# RcMPPT-Power_Module.net
KiCad netlist of a schematic drawn in Altium Designer
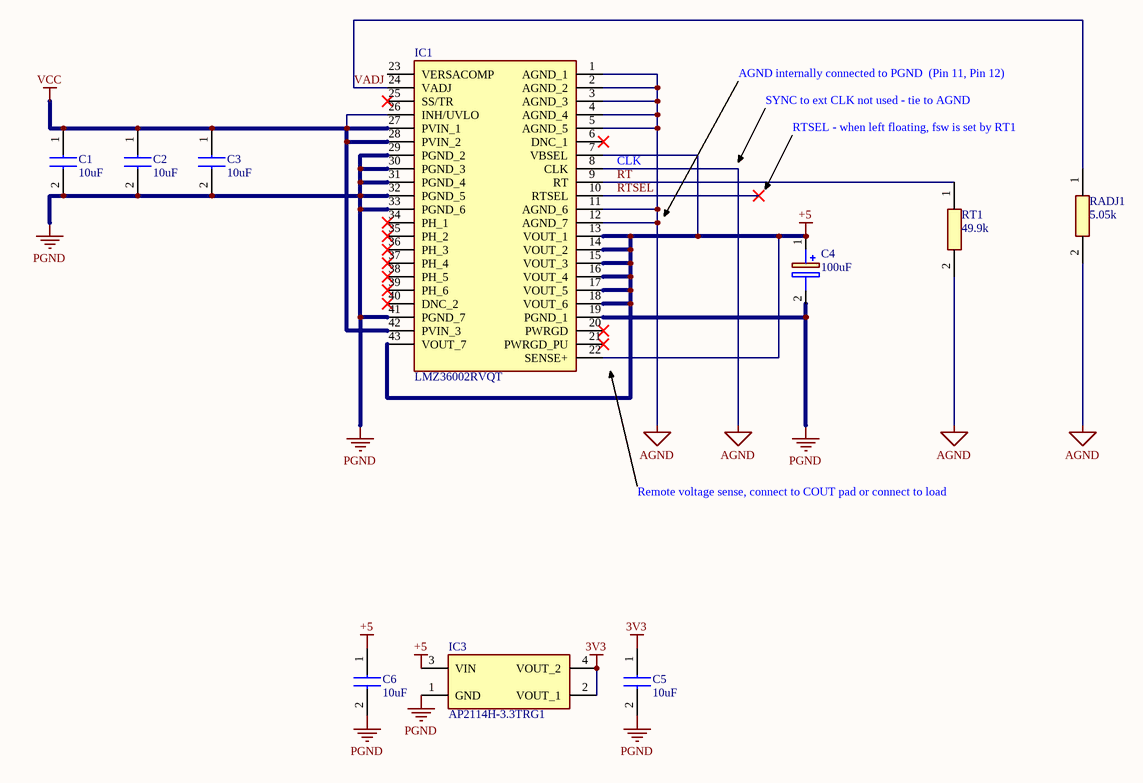
[diagram p0: RcMPPT-Power_Module.SchDoc]

(export (version "E")
  (design (tool "Eeschema 10.0.6"))
  (components
    (comp (ref "C1")
      (value "10uF")
      (footprint "RcMPPTLib:CAPC3225X280N")
      (description "Capacitor")
      (fields (field (name "MANUFACTURER_PART_NUMBER") "CL32B106KMVNNWE"))
      (libsource (lib "RcMPPTLib") (part "CL32B106KMVNNWE"))
    )
    (comp (ref "C2")
      (value "10uF")
      (footprint "RcMPPTLib:CAPC3225X280N")
      (description "Capacitor")
      (fields (field (name "MANUFACTURER_PART_NUMBER") "CL32B106KMVNNWE"))
      (libsource (lib "RcMPPTLib") (part "CL32B106KMVNNWE"))
    )
    (comp (ref "C3")
      (value "10uF")
      (footprint "RcMPPTLib:CAPC3225X280N")
      (description "Capacitor")
      (fields (field (name "MANUFACTURER_PART_NUMBER") "CL32B106KMVNNWE"))
      (libsource (lib "RcMPPTLib") (part "CL32B106KMVNNWE"))
    )
    (comp (ref "C4")
      (value "100uF")
      (footprint "CAPPM3528X200N")
      (description "Capacitor Polarised")
      (fields
        (field (name "MANUFACTURER_PART_NUMBER") "8TPE100MAZB")
        (field (name "MOUSER PART NUMBER") "667-8TPE100MAZB")
      )
      (libsource (lib "RcMPPTLib") (part "8TPE100MAZB"))
    )
    (comp (ref "C5")
      (value "10uF")
      (footprint "RcMPPTLib:CAPC3225X280N")
      (description "Capacitor")
      (fields (field (name "MANUFACTURER_PART_NUMBER") "CL32B106KMVNNWE"))
      (libsource (lib "RcMPPTLib") (part "CL32B106KMVNNWE"))
    )
    (comp (ref "C6")
      (value "10uF")
      (footprint "RcMPPTLib:CAPC3225X280N")
      (description "Capacitor")
      (fields (field (name "MANUFACTURER_PART_NUMBER") "CL32B106KMVNNWE"))
      (libsource (lib "RcMPPTLib") (part "CL32B106KMVNNWE"))
    )
    (comp (ref "IC1")
      (value "LMZ36002RVQT")
      (footprint "LMZ36002RVQR")
      (description "Integrated Circuit")
      (fields (field (name "MOUSER PART NUMBER") "595-LMZ36002RVQT"))
      (libsource (lib "RcMPPTLib") (part "LMZ36002RVQT"))
    )
    (comp (ref "IC3")
      (value "AP2114H-3.3TRG1")
      (footprint "SOT230P700X180-4N")
      (description "Integrated Circuit")
      (fields (field (name "MOUSER PART NUMBER") "621-AP2114H-3.3TRG1"))
      (libsource (lib "RcMPPTLib") (part "AP2114H-3.3TRG1"))
    )
    (comp (ref "RADJ1")
      (value "5.05k")
      (footprint "R0805")
      (description "Resistor")
      (fields
        (field (name "MANUFACTURER_PART_NUMBER") "RT0805BRD075K05L")
        (field (name "MOUSER PART NUMBER") "603-RT0805BRD075K05L")
      )
      (libsource (lib "RcMPPTLib") (part "RT0805BRD075K05L"))
    )
    (comp (ref "RT1")
      (value "49.9k")
      (footprint "RcMPPTLib:R0805")
      (description "Resistor")
      (fields
        (field (name "MANUFACTURER_PART_NUMBER") "ERJ-6ENF4992V")
        (field (name "MOUSER PART NUMBER") "667-ERJ-6ENF4992V")
      )
      (libsource (lib "RcMPPTLib") (part "ERJ-6ENF4992V"))
    )
  )
  (nets
    (net (code "1") (name "+5") (class "Default")
      (node (ref "C4") (pin "1") (pinfunction "+_1") (pintype "passive"))
      (node (ref "C6") (pin "1") (pinfunction "1_1") (pintype "passive"))
      (node (ref "IC1") (pin "13") (pinfunction "VOUT_1_13") (pintype "passive"))
      (node (ref "IC1") (pin "14") (pinfunction "VOUT_2_14") (pintype "passive"))
      (node (ref "IC1") (pin "15") (pinfunction "VOUT_3_15") (pintype "passive"))
      (node (ref "IC1") (pin "16") (pinfunction "VOUT_4_16") (pintype "passive"))
      (node (ref "IC1") (pin "17") (pinfunction "VOUT_5_17") (pintype "passive"))
      (node (ref "IC1") (pin "18") (pinfunction "VOUT_6_18") (pintype "passive"))
      (node (ref "IC1") (pin "22") (pinfunction "SENSE+_22") (pintype "passive"))
      (node (ref "IC1") (pin "43") (pinfunction "VOUT_7_43") (pintype "passive"))
      (node (ref "IC1") (pin "7") (pinfunction "VBSEL_7") (pintype "passive"))
      (node (ref "IC3") (pin "3") (pinfunction "VIN_3") (pintype "passive"))
    )
    (net (code "2") (name "/RT") (class "Default")
      (node (ref "IC1") (pin "9") (pinfunction "RT_9") (pintype "passive"))
      (node (ref "RT1") (pin "1") (pinfunction "1_1") (pintype "passive"))
    )
    (net (code "3") (name "/RTSEL") (class "Default")
      (node (ref "IC1") (pin "10") (pinfunction "RTSEL_10") (pintype "passive+no_connect"))
    )
    (net (code "4") (name "/VADJ") (class "Default")
      (node (ref "IC1") (pin "24") (pinfunction "VADJ_24") (pintype "passive"))
      (node (ref "RADJ1") (pin "1") (pinfunction "1_1") (pintype "passive"))
    )
    (net (code "5") (name "3V3") (class "Default")
      (node (ref "C5") (pin "1") (pinfunction "1_1") (pintype "passive"))
      (node (ref "IC3") (pin "2") (pinfunction "VOUT_1_2") (pintype "passive"))
      (node (ref "IC3") (pin "4") (pinfunction "VOUT_2_4") (pintype "passive"))
    )
    (net (code "6") (name "AGND") (class "Default")
      (node (ref "IC1") (pin "1") (pinfunction "AGND_1_1") (pintype "passive"))
      (node (ref "IC1") (pin "11") (pinfunction "AGND_6_11") (pintype "passive"))
      (node (ref "IC1") (pin "12") (pinfunction "AGND_7_12") (pintype "passive"))
      (node (ref "IC1") (pin "2") (pinfunction "AGND_2_2") (pintype "passive"))
      (node (ref "IC1") (pin "3") (pinfunction "AGND_3_3") (pintype "passive"))
      (node (ref "IC1") (pin "4") (pinfunction "AGND_4_4") (pintype "passive"))
      (node (ref "IC1") (pin "5") (pinfunction "AGND_5_5") (pintype "passive"))
      (node (ref "IC1") (pin "8") (pinfunction "CLK_8") (pintype "passive"))
      (node (ref "RADJ1") (pin "2") (pinfunction "2_2") (pintype "passive"))
      (node (ref "RT1") (pin "2") (pinfunction "2_2") (pintype "passive"))
    )
    (net (code "7") (name "PGND") (class "Default")
      (node (ref "C1") (pin "2") (pinfunction "2_2") (pintype "passive"))
      (node (ref "C2") (pin "2") (pinfunction "2_2") (pintype "passive"))
      (node (ref "C3") (pin "2") (pinfunction "2_2") (pintype "passive"))
      (node (ref "C4") (pin "2") (pinfunction "-_2") (pintype "passive"))
      (node (ref "C5") (pin "2") (pinfunction "2_2") (pintype "passive"))
      (node (ref "C6") (pin "2") (pinfunction "2_2") (pintype "passive"))
      (node (ref "IC1") (pin "19") (pinfunction "PGND_1_19") (pintype "passive"))
      (node (ref "IC1") (pin "29") (pinfunction "PGND_2_29") (pintype "passive"))
      (node (ref "IC1") (pin "30") (pinfunction "PGND_3_30") (pintype "passive"))
      (node (ref "IC1") (pin "31") (pinfunction "PGND_4_31") (pintype "passive"))
      (node (ref "IC1") (pin "32") (pinfunction "PGND_5_32") (pintype "passive"))
      (node (ref "IC1") (pin "33") (pinfunction "PGND_6_33") (pintype "passive"))
      (node (ref "IC1") (pin "41") (pinfunction "PGND_7_41") (pintype "passive"))
      (node (ref "IC3") (pin "1") (pinfunction "GND_1") (pintype "passive"))
    )
    (net (code "8") (name "VCC") (class "Default")
      (node (ref "C1") (pin "1") (pinfunction "1_1") (pintype "passive"))
      (node (ref "C2") (pin "1") (pinfunction "1_1") (pintype "passive"))
      (node (ref "C3") (pin "1") (pinfunction "1_1") (pintype "passive"))
      (node (ref "IC1") (pin "26") (pinfunction "INH/UVLO_26") (pintype "passive"))
      (node (ref "IC1") (pin "27") (pinfunction "PVIN_1_27") (pintype "passive"))
      (node (ref "IC1") (pin "28") (pinfunction "PVIN_2_28") (pintype "passive"))
      (node (ref "IC1") (pin "42") (pinfunction "PVIN_3_42") (pintype "passive"))
    )
    (net (code "9") (name "unconnected-(IC1-DNC_1-Pad6)") (class "Default")
      (node (ref "IC1") (pin "6") (pinfunction "DNC_1_6") (pintype "passive+no_connect"))
    )
    (net (code "10") (name "unconnected-(IC1-DNC_2-Pad40)") (class "Default")
      (node (ref "IC1") (pin "40") (pinfunction "DNC_2_40") (pintype "passive+no_connect"))
    )
    (net (code "11") (name "unconnected-(IC1-PH_1-Pad34)") (class "Default")
      (node (ref "IC1") (pin "34") (pinfunction "PH_1_34") (pintype "passive+no_connect"))
    )
    (net (code "12") (name "unconnected-(IC1-PH_2-Pad35)") (class "Default")
      (node (ref "IC1") (pin "35") (pinfunction "PH_2_35") (pintype "passive+no_connect"))
    )
    (net (code "13") (name "unconnected-(IC1-PH_3-Pad36)") (class "Default")
      (node (ref "IC1") (pin "36") (pinfunction "PH_3_36") (pintype "passive+no_connect"))
    )
    (net (code "14") (name "unconnected-(IC1-PH_4-Pad37)") (class "Default")
      (node (ref "IC1") (pin "37") (pinfunction "PH_4_37") (pintype "passive+no_connect"))
    )
    (net (code "15") (name "unconnected-(IC1-PH_5-Pad38)") (class "Default")
      (node (ref "IC1") (pin "38") (pinfunction "PH_5_38") (pintype "passive+no_connect"))
    )
    (net (code "16") (name "unconnected-(IC1-PH_6-Pad39)") (class "Default")
      (node (ref "IC1") (pin "39") (pinfunction "PH_6_39") (pintype "passive+no_connect"))
    )
    (net (code "17") (name "unconnected-(IC1-PWRGD-Pad20)") (class "Default")
      (node (ref "IC1") (pin "20") (pinfunction "PWRGD_20") (pintype "passive+no_connect"))
    )
    (net (code "18") (name "unconnected-(IC1-PWRGD_PU-Pad21)") (class "Default")
      (node (ref "IC1") (pin "21") (pinfunction "PWRGD_PU_21") (pintype "passive+no_connect"))
    )
    (net (code "19") (name "unconnected-(IC1-SS{slash}TR-Pad25)") (class "Default")
      (node (ref "IC1") (pin "25") (pinfunction "SS/TR_25") (pintype "passive+no_connect"))
    )
    (net (code "20") (name "unconnected-(IC1-VERSACOMP-Pad23)") (class "Default")
      (node (ref "IC1") (pin "23") (pinfunction "VERSACOMP_23") (pintype "passive"))
    )
  )
)
